# -5BuckConverter.net
KiCad netlist of a schematic drawn in Altium Designer
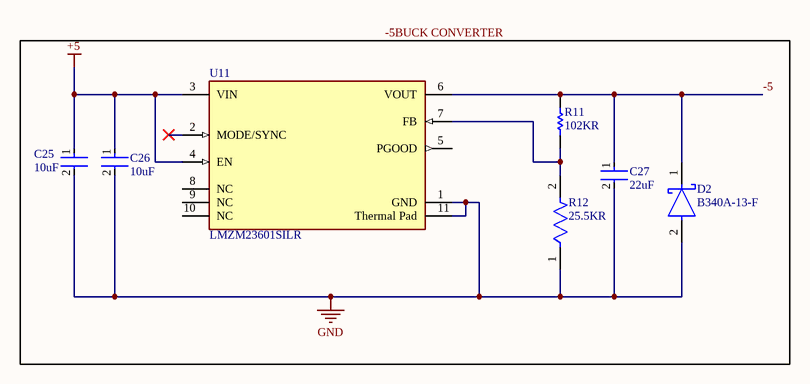
[diagram p0: -5BuckConverter.SchDoc]

(export (version "E")
  (design (tool "Eeschema 10.0.6"))
  (components
    (comp (ref "C25")
      (value "10uF")
      (footprint "FP-C1608-080-IPC_A")
      (description "CAP CER 10UF 25V X5R 0603")
      (fields (field (name "TOLERANCE") "20%"))
      (libsource (lib "Altium Content Vault") (part "11868f565c42a9108669ba33697ecf6"))
    )
    (comp (ref "C26")
      (value "10uF")
      (footprint "FP-C1608-080-IPC_A")
      (description "CAP CER 10UF 25V X5R 0603")
      (fields (field (name "TOLERANCE") "20%"))
      (libsource (lib "Altium Content Vault") (part "11868f565c42a9108669ba33697ecf6"))
    )
    (comp (ref "C27")
      (value "22uF")
      (footprint "FP-GRM21B-0_2-e0_2_0_7-IPC_C")
      (description "Chip Multilayer Ceramic Capacitors for General Purpose, 0805, 22uF, X5R, 15%, 20%, 10V")
      (fields (field (name "TOLERANCE") "20%") (field (name "VOLTAGE") "10V"))
      (libsource (lib "Altium Content Vault") (part "b4654b650e69147ec39a6b967a45e02"))
    )
    (comp (ref "D2")
      (value "B340A-13-F")
      (footprint "FP-SMA-MFG")
      (description "DIODE SCHOTTKY 40V 3A SMA")
      (fields (field (name "VOLTAGE") "40V"))
      (libsource (lib "Altium Content Vault") (part "1d6ec82d83fb6aee721767c19dac4b9"))
    )
    (comp (ref "R11")
      (value "102KR")
      (footprint "RESC1005X40X25ML05T05")
      (fields (field (name "MANUFACTURER") "Vishay Dale") (field (name "PART NUMBER") "CRCW0402102KFKED"))
      (libsource (lib "Altium Content Vault") (part "RES"))
    )
    (comp (ref "R12")
      (value "25.5KR")
      (footprint "FP-CRCW0402-e3-IPC_A")
      (description "RES Thick Film, 25.5kΩ, 1%, 0.063W, 100ppm/°C, 0402")
      (fields (field (name "TOLERANCE") "1%"))
      (libsource (lib "Altium Content Vault") (part "1029c3af85768c4190bb7ad29bc67b5"))
    )
    (comp (ref "U11")
      (value "LMZM23601SILR")
      (footprint "FP-SIL0010A-MFG")
      (description "DC DC CONVERTER 1.2-15V")
      (libsource (lib "Altium Content Vault") (part "0e66294c665cedcb0cad0e76d0c9cff"))
    )
  )
  (nets
    (net (code "1") (name "+5") (class "Default")
      (node (ref "C25") (pin "1") (pinfunction "1_1") (pintype "passive"))
      (node (ref "C26") (pin "1") (pinfunction "1_1") (pintype "passive"))
      (node (ref "U11") (pin "3") (pinfunction "VIN_3") (pintype "power_in"))
      (node (ref "U11") (pin "4") (pinfunction "EN_4") (pintype "input"))
    )
    (net (code "2") (name "/-5") (class "Default")
      (node (ref "C27") (pin "1") (pinfunction "1_1") (pintype "passive"))
      (node (ref "D2") (pin "1") (pinfunction "C_1") (pintype "passive"))
      (node (ref "R11") (pin "2") (pinfunction "2_2") (pintype "passive"))
      (node (ref "U11") (pin "6") (pinfunction "VOUT_6") (pintype "power_in"))
    )
    (net (code "4") (name "GND") (class "Default")
      (node (ref "C25") (pin "2") (pinfunction "2_2") (pintype "passive"))
      (node (ref "C26") (pin "2") (pinfunction "2_2") (pintype "passive"))
      (node (ref "C27") (pin "2") (pinfunction "2_2") (pintype "passive"))
      (node (ref "D2") (pin "2") (pinfunction "A_2") (pintype "passive"))
      (node (ref "R12") (pin "1") (pinfunction "1_1") (pintype "passive"))
      (node (ref "U11") (pin "1") (pinfunction "GND_1") (pintype "power_in"))
      (node (ref "U11") (pin "11") (pinfunction "Thermal_Pad_11") (pintype "power_in"))
    )
    (net (code "5") (name "Net-(U11-FB)") (class "Default")
      (node (ref "R11") (pin "1") (pinfunction "1_1") (pintype "passive"))
      (node (ref "R12") (pin "2") (pinfunction "2_2") (pintype "passive"))
      (node (ref "U11") (pin "7") (pinfunction "FB_7") (pintype "input"))
    )
    (net (code "6") (name "unconnected-(U11-MODE{slash}SYNC-Pad2)") (class "Default")
      (node (ref "U11") (pin "2") (pinfunction "MODE/SYNC_2") (pintype "input+no_connect"))
    )
    (net (code "7") (name "unconnected-(U11-NC-Pad8)") (class "Default")
      (node (ref "U11") (pin "8") (pinfunction "NC_8") (pintype "passive"))
    )
    (net (code "8") (name "unconnected-(U11-NC-Pad9)") (class "Default")
      (node (ref "U11") (pin "9") (pinfunction "NC_9") (pintype "passive"))
    )
    (net (code "9") (name "unconnected-(U11-NC-Pad10)") (class "Default")
      (node (ref "U11") (pin "10") (pinfunction "NC_10") (pintype "passive"))
    )
    (net (code "10") (name "unconnected-(U11-PGOOD-Pad5)") (class "Default")
      (node (ref "U11") (pin "5") (pinfunction "PGOOD_5") (pintype "output"))
    )
  )
)
